# 05-WPT.net
KiCad netlist of a schematic drawn in Altium Designer
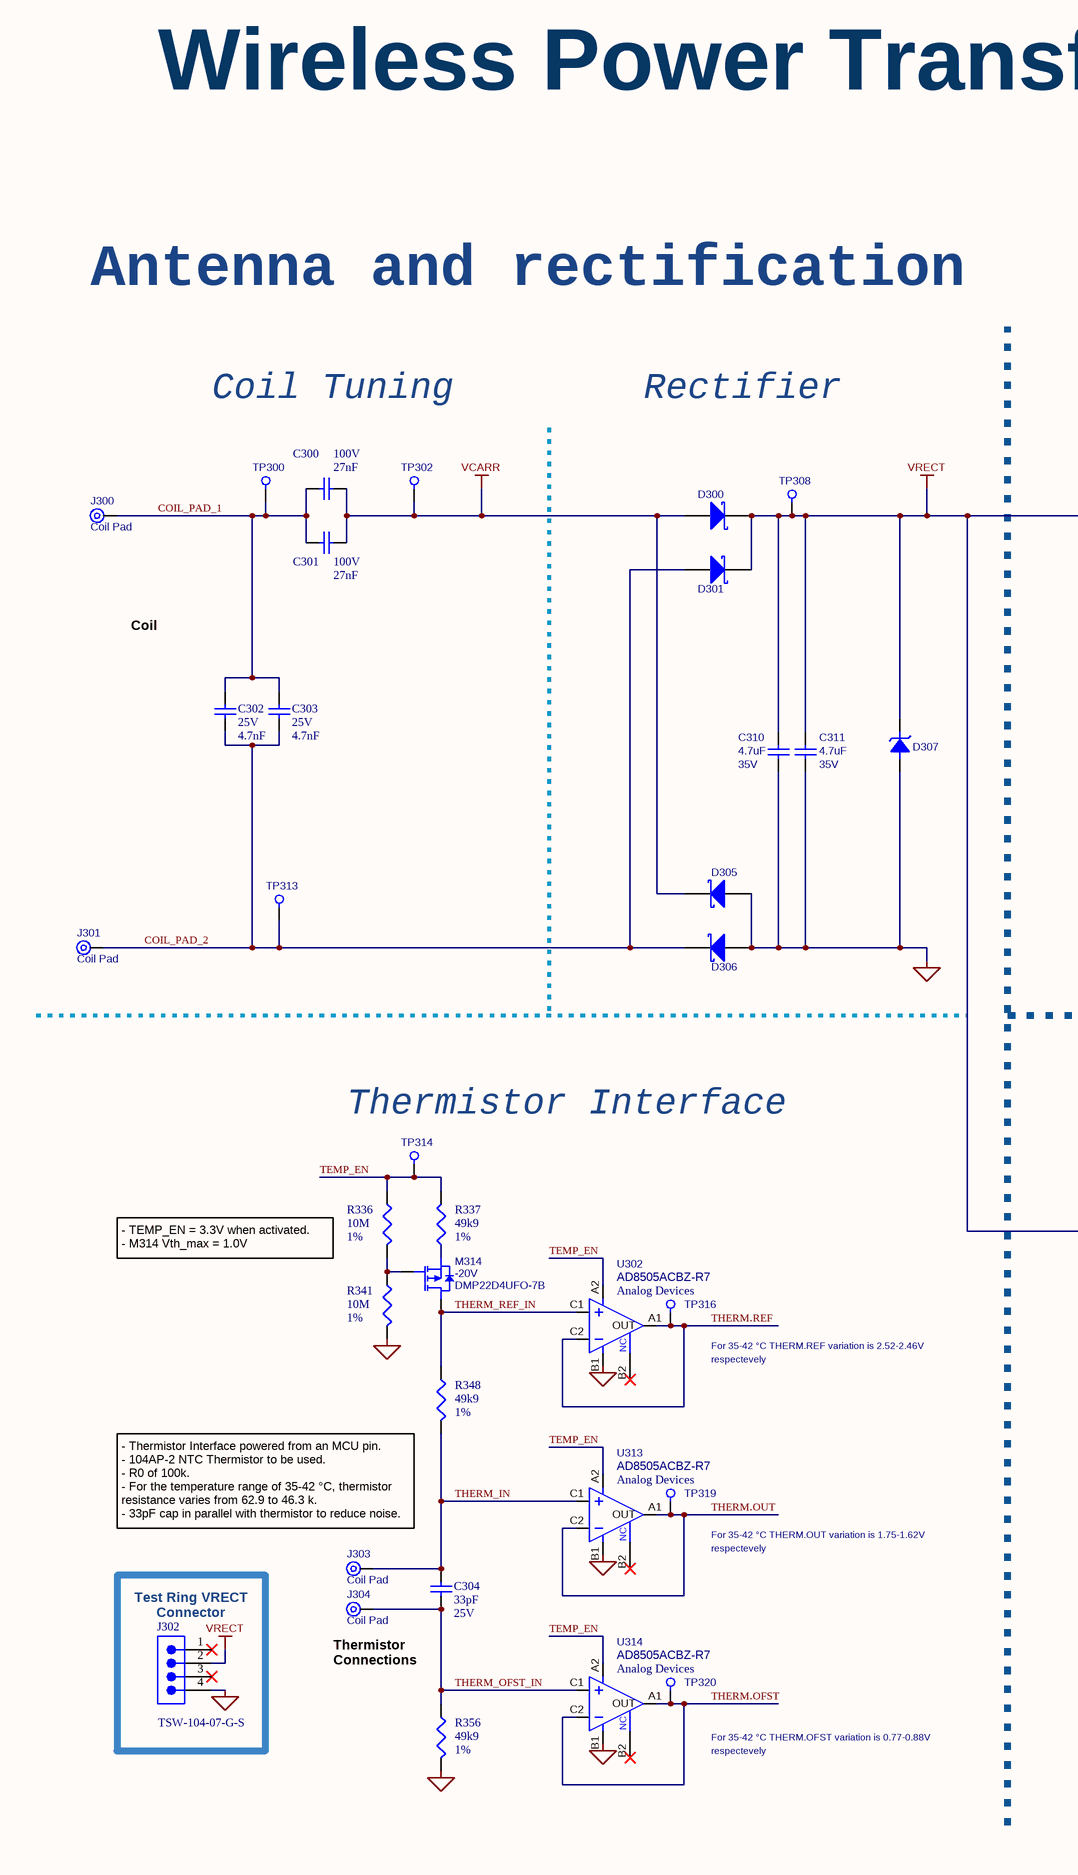
[diagram p0: 05-WPT.SchDoc, left]
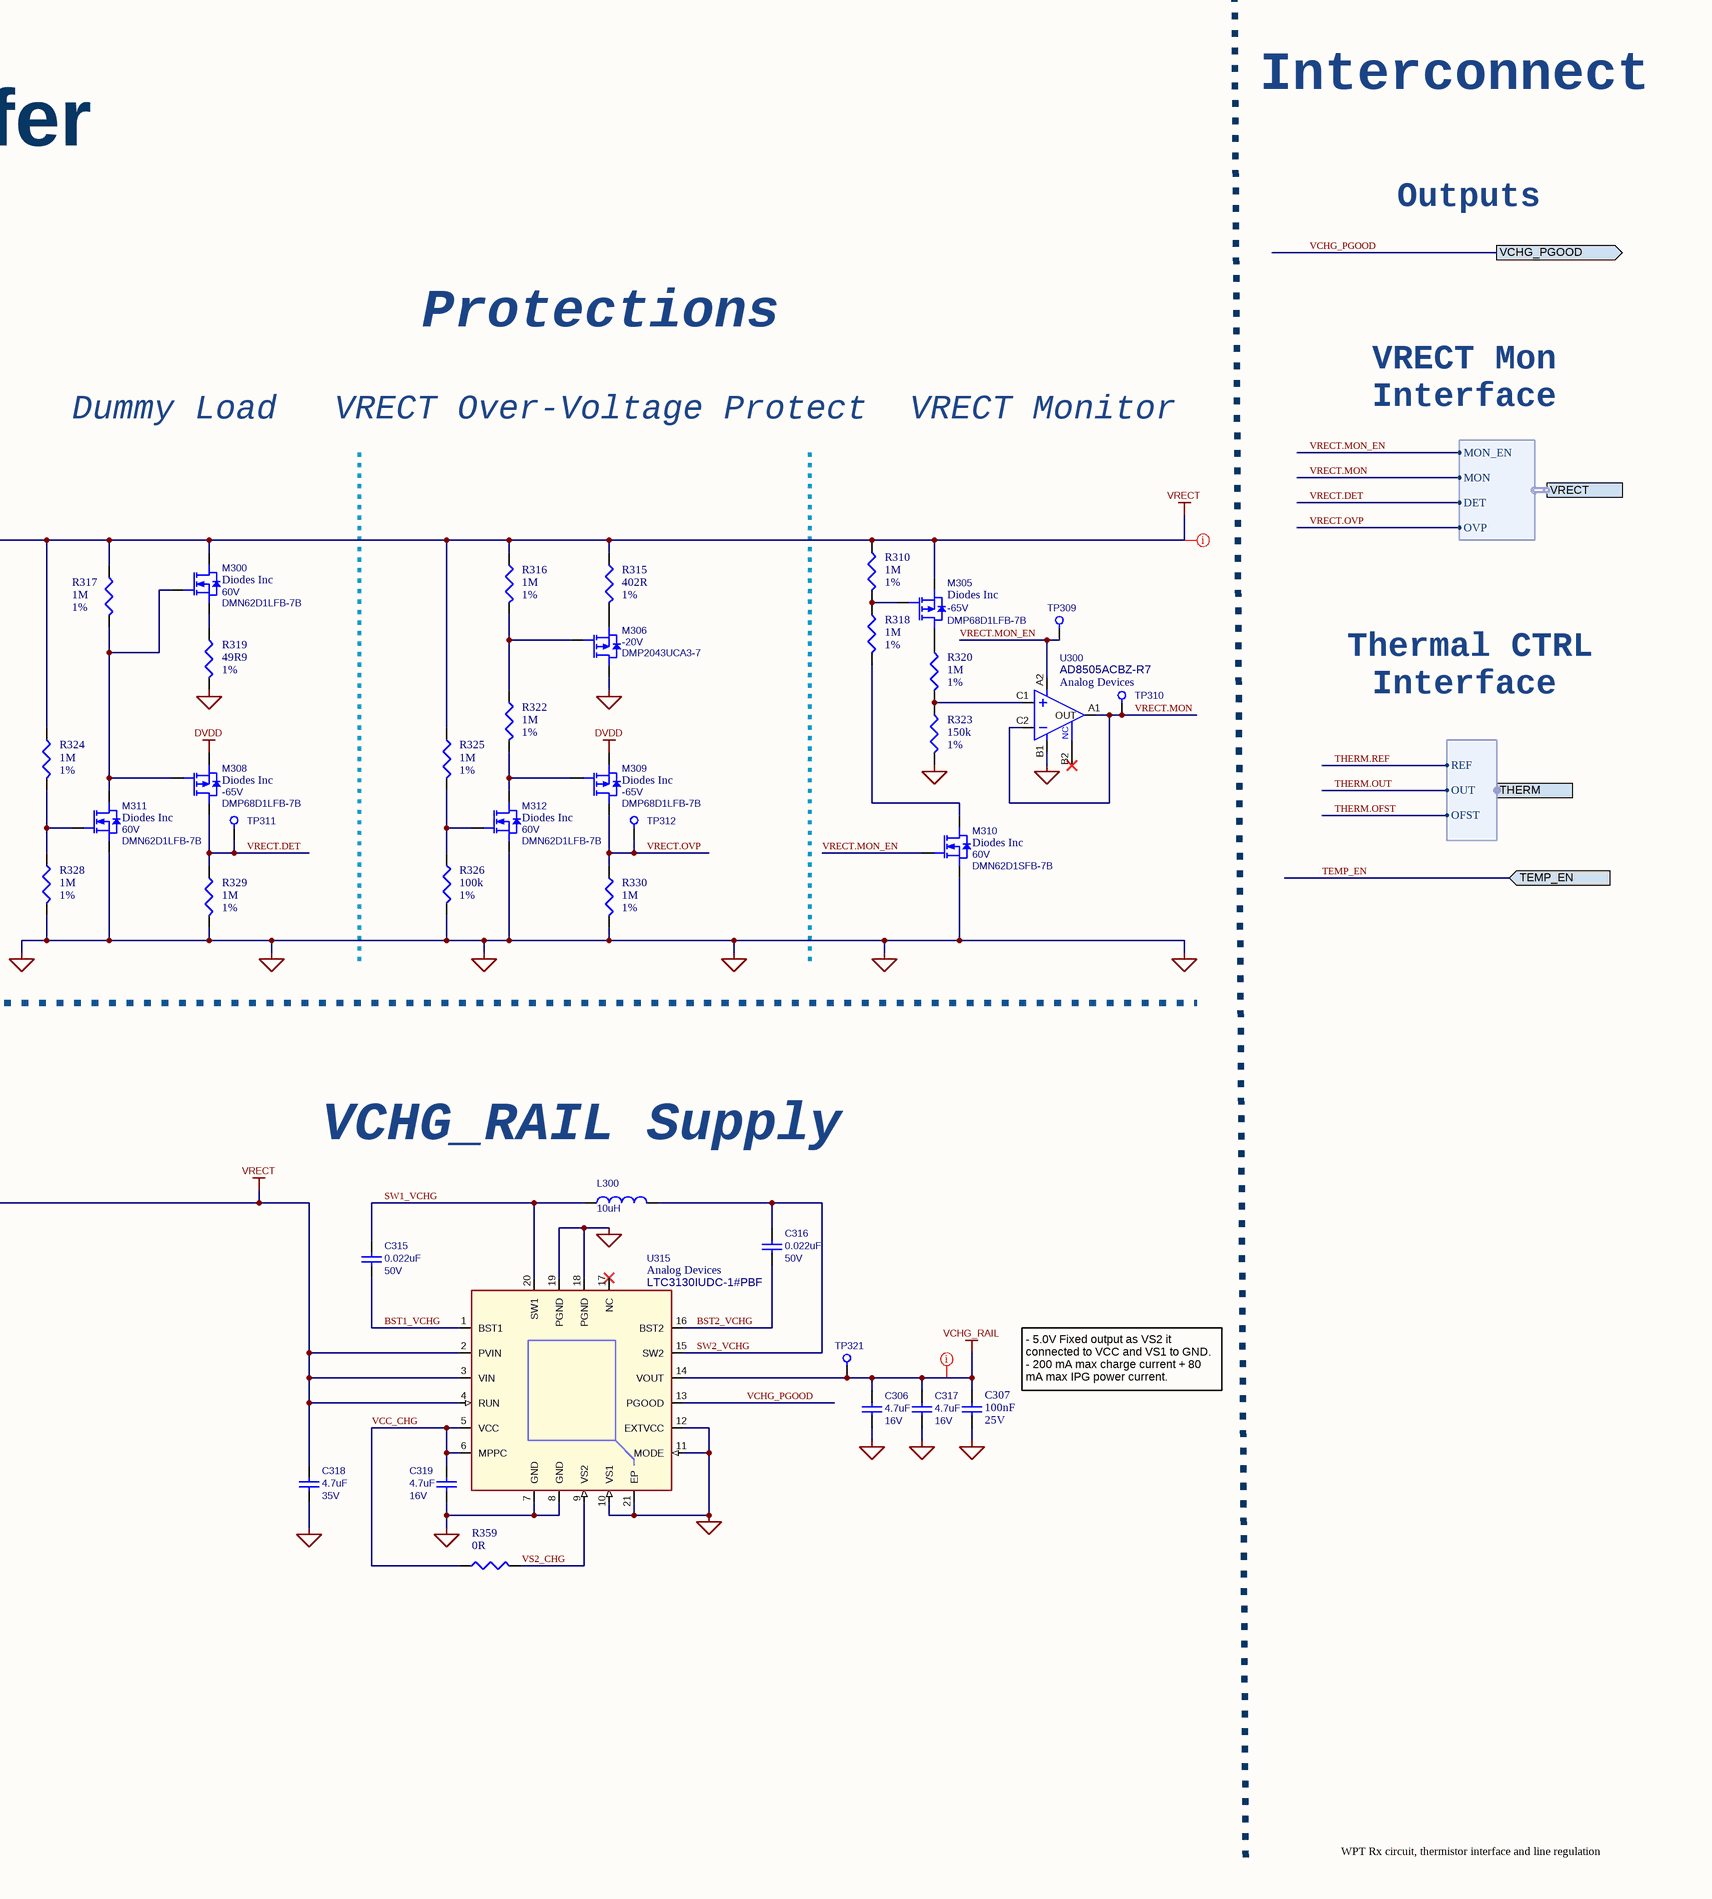
[diagram p1: 05-WPT.SchDoc, right]

(export (version "E")
  (design (tool "Eeschema 10.0.6"))
  (components
    (comp (ref "C300")
      (value "27nF")
      (footprint "CAP0805_REDUCED")
      (description "Capacitor, 27nF, C0G, 100VDC, 2%, 0805, Implant-grade")
      (fields
        (field (name "MANUFACTURER") "Murata")
        (field (name "MANUFACTURER PART NUMBER") "GRM2195C2A273GE01D")
        (field (name "VOLTAGE RATING") "100V")
      )
      (libsource (lib "MP-LIBRARY") (part "GRM2195C2A273GE01D"))
    )
    (comp (ref "C301")
      (value "27nF")
      (footprint "CAP0805_REDUCED")
      (description "Capacitor, 27nF, C0G, 100VDC, 2%, 0805, Implant-grade")
      (fields
        (field (name "MANUFACTURER") "Murata")
        (field (name "MANUFACTURER PART NUMBER") "GRM2195C2A273GE01D")
        (field (name "VOLTAGE RATING") "100V")
      )
      (libsource (lib "MP-LIBRARY") (part "GRM2195C2A273GE01D"))
    )
    (comp (ref "C302")
      (value "4.7nF")
      (footprint "CAP0603_REDUCED")
      (description "Capacitor, 4.7nF, C0G, 25V, 1%, 0603, Implant-grade")
      (fields
        (field (name "MANUFACTURER") "KEMET")
        (field (name "MANUFACTURER PART NUMBER") "C0603C472F3GECTU")
        (field (name "VOLTAGE RATING") "25V")
      )
      (libsource (lib "MP-LIBRARY") (part "C0603C472F3GECTU"))
    )
    (comp (ref "C303")
      (value "4.7nF")
      (footprint "CAP0603_REDUCED")
      (description "Capacitor, 4.7nF, C0G, 25V, 1%, 0603, Implant-grade")
      (fields
        (field (name "MANUFACTURER") "KEMET")
        (field (name "MANUFACTURER PART NUMBER") "C0603C472F3GECTU")
        (field (name "VOLTAGE RATING") "25V")
      )
      (libsource (lib "MP-LIBRARY") (part "C0603C472F3GECTU"))
    )
    (comp (ref "C304")
      (value "33pF")
      (footprint "C0201_C")
      (fields
        (field (name "MANUFACTURER") "Murata")
        (field (name "MANUFACTURER PART NUMBER") "GRM0335C1E330JA01D")
        (field (name "RATED DC VOLTAGE (URDC)") "25V")
      )
      (libsource (lib "MP-LIBRARY") (part "GRM0335C1E330JA01D"))
    )
    (comp (ref "C306")
      (value "4.7uF")
      (footprint "CAP0603_REDUCED")
      (description "Capacitor, 4.7uF, X5R, 16V, 10%, 0603, Implant-grade")
      (fields
        (field (name "MANUFACTURER") "Murata")
        (field (name "RATING") "16V")
        (field (name "MANUFACTURER PART NUMBER") "GRM188R61C475KE11")
      )
      (libsource (lib "MP-LIBRARY") (part "GRM188R61C475KE11"))
    )
    (comp (ref "C307")
      (value "100nF")
      (footprint "C0201_C")
      (fields
        (field (name "MANUFACTURER") "Murata")
        (field (name "MANUFACTURER PART NUMBER") "GRM033R61E104KE14J")
        (field (name "RATED DC VOLTAGE (URDC)") "25V")
      )
      (libsource (lib "MP-LIBRARY") (part "GRM033R61E104KE14J"))
    )
    (comp (ref "C310")
      (value "4.7uF")
      (footprint "CAP0805_REDUCED")
      (description "Capacitor, 4.7uF, X7S, 35V, 10%, 0805, Implant-grade")
      (fields
        (field (name "MANUFACTURER") "Murata")
        (field (name "RATING") "35V")
        (field (name "MANUFACTURER PART NUMBER") "GCM21BC7YA475KE36L")
      )
      (libsource (lib "MP-LIBRARY") (part "GCM21BC7YA475KE36L"))
    )
    (comp (ref "C311")
      (value "4.7uF")
      (footprint "CAP0805_REDUCED")
      (description "Capacitor, 4.7uF, X7S, 35V, 10%, 0805, Implant-grade")
      (fields
        (field (name "MANUFACTURER") "Murata")
        (field (name "RATING") "35V")
        (field (name "MANUFACTURER PART NUMBER") "GCM21BC7YA475KE36L")
      )
      (libsource (lib "MP-LIBRARY") (part "GCM21BC7YA475KE36L"))
    )
    (comp (ref "C315")
      (value "0.022uF")
      (footprint "CAP0402_REDUCED")
      (description "Capacitor, 0.022uF, X7R, 50V, 10%, 0402, Implant-grade")
      (fields
        (field (name "MANUFACTURER") "Murata")
        (field (name "RATING") "50V")
        (field (name "MANUFACTURER PART NUMBER") "GCM155R71H223KA55")
      )
      (libsource (lib "MP-LIBRARY") (part "GCM155R71H223KA55D"))
    )
    (comp (ref "C316")
      (value "0.022uF")
      (footprint "CAP0402_REDUCED")
      (description "Capacitor, 0.022uF, X7R, 50V, 10%, 0402, Implant-grade")
      (fields
        (field (name "MANUFACTURER") "Murata")
        (field (name "RATING") "50V")
        (field (name "MANUFACTURER PART NUMBER") "GCM155R71H223KA55")
      )
      (libsource (lib "MP-LIBRARY") (part "GCM155R71H223KA55D"))
    )
    (comp (ref "C317")
      (value "4.7uF")
      (footprint "CAP0603_REDUCED")
      (description "Capacitor, 4.7uF, X5R, 16V, 10%, 0603, Implant-grade")
      (fields
        (field (name "MANUFACTURER") "Murata")
        (field (name "RATING") "16V")
        (field (name "MANUFACTURER PART NUMBER") "GRM188R61C475KE11")
      )
      (libsource (lib "MP-LIBRARY") (part "GRM188R61C475KE11"))
    )
    (comp (ref "C318")
      (value "4.7uF")
      (footprint "CAP0805_REDUCED")
      (description "Capacitor, 4.7uF, X7S, 35V, 10%, 0805, Implant-grade")
      (fields
        (field (name "MANUFACTURER") "Murata")
        (field (name "RATING") "35V")
        (field (name "MANUFACTURER PART NUMBER") "GCM21BC7YA475KE36L")
      )
      (libsource (lib "MP-LIBRARY") (part "GCM21BC7YA475KE36L"))
    )
    (comp (ref "C319")
      (value "4.7uF")
      (footprint "CAP0603_REDUCED")
      (description "Capacitor, 4.7uF, X5R, 16V, 10%, 0603, Implant-grade")
      (fields
        (field (name "MANUFACTURER") "Murata")
        (field (name "RATING") "16V")
        (field (name "MANUFACTURER PART NUMBER") "GRM188R61C475KE11")
      )
      (libsource (lib "MP-LIBRARY") (part "GRM188R61C475KE11"))
    )
    (comp (ref "D300")
      (value "NSR05T40XV2T5G")
      (footprint "STM_SOD-523_R")
      (description "Schottky, 40V, 500mA, 530mV, SOD-523")
      (fields (field (name "MANUFACTURER") "ON Semiconductor"))
      (libsource (lib "MP-LIBRARY") (part "NSR05T40XV2T5G"))
    )
    (comp (ref "D301")
      (value "NSR05T40XV2T5G")
      (footprint "STM_SOD-523_R")
      (description "Schottky, 40V, 500mA, 530mV, SOD-523")
      (fields (field (name "MANUFACTURER") "ON Semiconductor"))
      (libsource (lib "MP-LIBRARY") (part "NSR05T40XV2T5G"))
    )
    (comp (ref "D305")
      (value "NSR05T40XV2T5G")
      (footprint "STM_SOD-523_R")
      (description "Schottky, 40V, 500mA, 530mV, SOD-523")
      (fields (field (name "MANUFACTURER") "ON Semiconductor"))
      (libsource (lib "MP-LIBRARY") (part "NSR05T40XV2T5G"))
    )
    (comp (ref "D306")
      (value "NSR05T40XV2T5G")
      (footprint "STM_SOD-523_R")
      (description "Schottky, 40V, 500mA, 530mV, SOD-523")
      (fields (field (name "MANUFACTURER") "ON Semiconductor"))
      (libsource (lib "MP-LIBRARY") (part "NSR05T40XV2T5G"))
    )
    (comp (ref "D307")
      (value "BZX884B10L-G3-08")
      (footprint "DFN1006-2A")
      (description "Zener Diode 10 V 300 mW ±2% Surface Mount DFN1006-2A 0402")
      (fields (field (name "MANUFACTURER") "Vishay"))
      (libsource (lib "MP-LIBRARY") (part "BZX884B10L-G3-08"))
    )
    (comp (ref "J300")
      (value "Coil Pad")
      (footprint "FEEDHOLE_20mil")
      (description "Coil TH pad, hole size and ring TBD")
      (libsource (lib "MP-LIBRARY") (part "Coil Pad"))
    )
    (comp (ref "J301")
      (value "Coil Pad")
      (footprint "FEEDHOLE_20mil")
      (description "Coil TH pad, hole size and ring TBD")
      (libsource (lib "MP-LIBRARY") (part "Coil Pad"))
    )
    (comp (ref "J302")
      (value "TSW-104-07-G-S")
      (footprint "SMTC-TSW-104-07-X-S")
      (fields (field (name "MANUFACTURER") "Samtec") (field (name "PARTNUMBER") "TSW-106-07-G-S"))
      (libsource (lib "MP-LIBRARY") (part "TSW-104-07-G-S"))
    )
    (comp (ref "J303")
      (value "Coil Pad")
      (footprint "FEEDHOLE_20mil")
      (description "Coil TH pad, hole size and ring TBD")
      (libsource (lib "MP-LIBRARY") (part "Coil Pad"))
    )
    (comp (ref "J304")
      (value "Coil Pad")
      (footprint "FEEDHOLE_20mil")
      (description "Coil TH pad, hole size and ring TBD")
      (libsource (lib "MP-LIBRARY") (part "Coil Pad"))
    )
    (comp (ref "L300")
      (value "10uH")
      (footprint "WURTH_74438323100_REDUCED")
      (description "Inductor, 10uH, 600mA, 20%, 1008")
      (fields (field (name "MANUFACTURER") "Wurth") (field (name "MANUFACTURER PART NUMBER") "74438323100"))
      (libsource (lib "MP-LIBRARY") (part "74438323100"))
    )
    (comp (ref "M300")
      (value "DMN62D1LFB-7B")
      (footprint "DIODESINC_X1-DFN1006-3")
      (description "MOSFET, N-Chan, 60V, 320mA, DFN1006")
      (fields (field (name "MANUFACTURER") "Diodes Inc") (field (name "RATING") "60V"))
      (libsource (lib "MP-LIBRARY") (part "DMN62D1LFB-7B"))
    )
    (comp (ref "M305")
      (value "DMP68D1LFB-7B")
      (footprint "DIODESINC_X1-DFN1006-3")
      (description "MOSFET, P-chan, -65V, -290mA, DFN1006")
      (fields
        (field (name "MANUFACTURER") "Diodes Inc")
        (field (name "RATING") "-65V")
        (field (name "MANUFACTURER PART NUMBER") "DMP68D1LFB")
      )
      (libsource (lib "MP-LIBRARY") (part "DMP68D1LFB-7B"))
    )
    (comp (ref "M306")
      (value "DMP2043UCA3-7")
      (footprint "DIODESINC_X2-DSN1010-3_CUSTOMPIN")
      (description "MOSFET, P-chan, -20V, -3.4A, DFN1010-3")
      (fields (field (name "MANUFACTURER") "Diodes Inc") (field (name "RATING") "-20V"))
      (libsource (lib "MP-LIBRARY") (part "DMP2043UCA3-7"))
    )
    (comp (ref "M308")
      (value "DMP68D1LFB-7B")
      (footprint "DIODESINC_X1-DFN1006-3")
      (description "MOSFET, P-chan, -65V, -290mA, DFN1006")
      (fields
        (field (name "MANUFACTURER") "Diodes Inc")
        (field (name "RATING") "-65V")
        (field (name "MANUFACTURER PART NUMBER") "DMP68D1LFB")
      )
      (libsource (lib "MP-LIBRARY") (part "DMP68D1LFB-7B"))
    )
    (comp (ref "M309")
      (value "DMP68D1LFB-7B")
      (footprint "DIODESINC_X1-DFN1006-3")
      (description "MOSFET, P-chan, -65V, -290mA, DFN1006")
      (fields
        (field (name "MANUFACTURER") "Diodes Inc")
        (field (name "RATING") "-65V")
        (field (name "MANUFACTURER PART NUMBER") "DMP68D1LFB")
      )
      (libsource (lib "MP-LIBRARY") (part "DMP68D1LFB-7B"))
    )
    (comp (ref "M310")
      (value "DMN62D1SFB-7B")
      (footprint "DIODESINC_X1-DFN1006-3")
      (description "MOSFET, N-Chan, 60V, 300mA, DFN1006")
      (fields (field (name "MANUFACTURER") "Diodes Inc") (field (name "RATING") "60V"))
      (libsource (lib "MP-LIBRARY") (part "DMN62D1SFB-7B"))
    )
    (comp (ref "M311")
      (value "DMN62D1LFB-7B")
      (footprint "DIODESINC_X1-DFN1006-3")
      (description "MOSFET, N-Chan, 60V, 320mA, DFN1006")
      (fields (field (name "MANUFACTURER") "Diodes Inc") (field (name "RATING") "60V"))
      (libsource (lib "MP-LIBRARY") (part "DMN62D1LFB-7B"))
    )
    (comp (ref "M312")
      (value "DMN62D1LFB-7B")
      (footprint "DIODESINC_X1-DFN1006-3")
      (description "MOSFET, N-Chan, 60V, 320mA, DFN1006")
      (fields (field (name "MANUFACTURER") "Diodes Inc") (field (name "RATING") "60V"))
      (libsource (lib "MP-LIBRARY") (part "DMN62D1LFB-7B"))
    )
    (comp (ref "M314")
      (value "DMP22D4UFO-7B")
      (footprint "DIODESINC_X2-DFN0604-3")
      (description "MOSFET, P-chan, -20V, -383mA, DFN0604")
      (fields (field (name "MANUFACTURER") "Diodes Inc") (field (name "RATING") "-20V"))
      (libsource (lib "MP-LIBRARY") (part "DMP22D4UFO-7B"))
    )
    (comp (ref "R310")
      (value "1M")
      (footprint "R0201_C")
      (fields
        (field (name "MANUFACTURER") "Vishay")
        (field (name "MANUFACTURER PART NUMBER") "CRCW02011M00FNED")
        (field (name "TOLERANCE") "1%")
        (field (name "POWER") "50mW")
      )
      (libsource (lib "MP-LIBRARY") (part "CRCW02011M00FNED"))
    )
    (comp (ref "R315")
      (value "402R")
      (footprint "R0201_C")
      (fields
        (field (name "MANUFACTURER") "Vishay")
        (field (name "MANUFACTURER PART NUMBER") "CRCW0201402RFNED")
        (field (name "TOLERANCE") "1%")
        (field (name "POWER") "50mW")
      )
      (libsource (lib "MP-LIBRARY") (part "CRCW0201402RFNED"))
    )
    (comp (ref "R316")
      (value "1M")
      (footprint "R0201_C")
      (fields
        (field (name "MANUFACTURER") "Vishay")
        (field (name "MANUFACTURER PART NUMBER") "CRCW02011M00FNED")
        (field (name "TOLERANCE") "1%")
        (field (name "POWER") "50mW")
      )
      (libsource (lib "MP-LIBRARY") (part "CRCW02011M00FNED"))
    )
    (comp (ref "R317")
      (value "1M")
      (footprint "R0201_C")
      (fields
        (field (name "MANUFACTURER") "Vishay")
        (field (name "MANUFACTURER PART NUMBER") "CRCW02011M00FNED")
        (field (name "TOLERANCE") "1%")
        (field (name "POWER") "50mW")
      )
      (libsource (lib "MP-LIBRARY") (part "CRCW02011M00FNED"))
    )
    (comp (ref "R318")
      (value "1M")
      (footprint "R0201_C")
      (fields
        (field (name "MANUFACTURER") "Vishay")
        (field (name "MANUFACTURER PART NUMBER") "CRCW02011M00FNED")
        (field (name "TOLERANCE") "1%")
        (field (name "POWER") "50mW")
      )
      (libsource (lib "MP-LIBRARY") (part "CRCW02011M00FNED"))
    )
    (comp (ref "R319")
      (value "49R9")
      (footprint "R0201_C")
      (fields
        (field (name "MANUFACTURER") "Vishay")
        (field (name "MANUFACTURER PART NUMBER") "CRCW020149R9FNED")
        (field (name "TOLERANCE") "1%")
        (field (name "POWER") "50mW")
      )
      (libsource (lib "MP-LIBRARY") (part "CRCW020149R9FNED"))
    )
    (comp (ref "R320")
      (value "1M")
      (footprint "R0201_C")
      (fields
        (field (name "MANUFACTURER") "Vishay")
        (field (name "MANUFACTURER PART NUMBER") "CRCW02011M00FNED")
        (field (name "TOLERANCE") "1%")
        (field (name "POWER") "50mW")
      )
      (libsource (lib "MP-LIBRARY") (part "CRCW02011M00FNED"))
    )
    (comp (ref "R322")
      (value "1M")
      (footprint "R0201_C")
      (fields
        (field (name "MANUFACTURER") "Vishay")
        (field (name "MANUFACTURER PART NUMBER") "CRCW02011M00FNED")
        (field (name "TOLERANCE") "1%")
        (field (name "POWER") "50mW")
      )
      (libsource (lib "MP-LIBRARY") (part "CRCW02011M00FNED"))
    )
    (comp (ref "R323")
      (value "150k")
      (footprint "R0201_C")
      (fields
        (field (name "MANUFACTURER") "Vishay")
        (field (name "MANUFACTURER PART NUMBER") "CRCW0201150KFNED")
        (field (name "TOLERANCE") "1%")
        (field (name "POWER") "50mW")
      )
      (libsource (lib "MP-LIBRARY") (part "CRCW0201150KFNED"))
    )
    (comp (ref "R324")
      (value "1M")
      (footprint "R0201_C")
      (fields
        (field (name "MANUFACTURER") "Vishay")
        (field (name "MANUFACTURER PART NUMBER") "CRCW02011M00FNED")
        (field (name "TOLERANCE") "1%")
        (field (name "POWER") "50mW")
      )
      (libsource (lib "MP-LIBRARY") (part "CRCW02011M00FNED"))
    )
    (comp (ref "R325")
      (value "1M")
      (footprint "R0201_C")
      (fields
        (field (name "MANUFACTURER") "Vishay")
        (field (name "MANUFACTURER PART NUMBER") "CRCW02011M00FNED")
        (field (name "TOLERANCE") "1%")
        (field (name "POWER") "50mW")
      )
      (libsource (lib "MP-LIBRARY") (part "CRCW02011M00FNED"))
    )
    (comp (ref "R326")
      (value "100k")
      (footprint "R0201_C")
      (fields
        (field (name "MANUFACTURER") "Vishay")
        (field (name "MANUFACTURER PART NUMBER") "CRCW0201100KFNED")
        (field (name "TOLERANCE") "1%")
        (field (name "POWER") "50mW")
      )
      (libsource (lib "MP-LIBRARY") (part "CRCW0201100KFNED"))
    )
    (comp (ref "R328")
      (value "1M")
      (footprint "R0201_C")
      (fields
        (field (name "MANUFACTURER") "Vishay")
        (field (name "MANUFACTURER PART NUMBER") "CRCW02011M00FNED")
        (field (name "TOLERANCE") "1%")
        (field (name "POWER") "50mW")
      )
      (libsource (lib "MP-LIBRARY") (part "CRCW02011M00FNED"))
    )
    (comp (ref "R329")
      (value "1M")
      (footprint "R0201_C")
      (fields
        (field (name "MANUFACTURER") "Vishay")
        (field (name "MANUFACTURER PART NUMBER") "CRCW02011M00FNED")
        (field (name "TOLERANCE") "1%")
        (field (name "POWER") "50mW")
      )
      (libsource (lib "MP-LIBRARY") (part "CRCW02011M00FNED"))
    )
    (comp (ref "R330")
      (value "1M")
      (footprint "R0201_C")
      (fields
        (field (name "MANUFACTURER") "Vishay")
        (field (name "MANUFACTURER PART NUMBER") "CRCW02011M00FNED")
        (field (name "TOLERANCE") "1%")
        (field (name "POWER") "50mW")
      )
      (libsource (lib "MP-LIBRARY") (part "CRCW02011M00FNED"))
    )
    (comp (ref "R336")
      (value "10M")
      (footprint "R0201_C")
      (fields
        (field (name "MANUFACTURER") "Vishay Draloric")
        (field (name "MANUFACTURER PART NUMBER") "CRCW020110M0FNED")
        (field (name "TOLERANCE") "1%")
        (field (name "POWER") "50mW")
      )
      (libsource (lib "MP-LIBRARY") (part "CRCW020110M0FNED"))
    )
    (comp (ref "R337")
      (value "49k9")
      (footprint "R0201_C")
      (fields
        (field (name "MANUFACTURER") "Vishay")
        (field (name "MANUFACTURER PART NUMBER") "CRCW020149K9FNED")
        (field (name "TOLERANCE") "1%")
        (field (name "POWER") "50mW")
      )
      (libsource (lib "MP-LIBRARY") (part "CRCW020149K9FNED"))
    )
    (comp (ref "R341")
      (value "10M")
      (footprint "R0201_C")
      (fields
        (field (name "MANUFACTURER") "Vishay Draloric")
        (field (name "MANUFACTURER PART NUMBER") "CRCW020110M0FNED")
        (field (name "TOLERANCE") "1%")
        (field (name "POWER") "50mW")
      )
      (libsource (lib "MP-LIBRARY") (part "CRCW020110M0FNED"))
    )
    (comp (ref "R348")
      (value "49k9")
      (footprint "R0201_C")
      (fields
        (field (name "MANUFACTURER") "Vishay")
        (field (name "MANUFACTURER PART NUMBER") "CRCW020149K9FNED")
        (field (name "TOLERANCE") "1%")
        (field (name "POWER") "50mW")
      )
      (libsource (lib "MP-LIBRARY") (part "CRCW020149K9FNED"))
    )
    (comp (ref "R356")
      (value "49k9")
      (footprint "R0201_C")
      (fields
        (field (name "MANUFACTURER") "Vishay")
        (field (name "MANUFACTURER PART NUMBER") "CRCW020149K9FNED")
        (field (name "TOLERANCE") "1%")
        (field (name "POWER") "50mW")
      )
      (libsource (lib "MP-LIBRARY") (part "CRCW020149K9FNED"))
    )
    (comp (ref "R359")
      (value "0R")
      (footprint "R0201_C")
      (description "Fixed Resistor, Metal Glaze/thick Film, 0.05W, 0ohm, Surface Mount, 0201")
      (fields
        (field (name "MANUFACTURER") "Vishay")
        (field (name "MANUFACTURER PART NUMBER") "CRCW02010000Z0ED")
      )
      (libsource (lib "MP-LIBRARY") (part "CRCW02010000Z0ED"))
    )
    (comp (ref "TP300")
      (value "Test Point")
      (footprint "testpad_0.9mm")
      (description "Test pad, 0.90mm circular pad")
      (libsource (lib "MP-LIBRARY") (part "Test Point"))
    )
    (comp (ref "TP302")
      (value "Test Point")
      (footprint "testpad_0.9mm")
      (description "Test pad, 0.90mm circular pad")
      (libsource (lib "MP-LIBRARY") (part "Test Point"))
    )
    (comp (ref "TP308")
      (value "Test Point")
      (footprint "testpad_0.9mm")
      (description "Test pad, 0.90mm circular pad")
      (libsource (lib "MP-LIBRARY") (part "Test Point"))
    )
    (comp (ref "TP309")
      (value "Test Point")
      (footprint "testpad_0.9mm")
      (description "Test pad, 0.90mm circular pad")
      (libsource (lib "MP-LIBRARY") (part "Test Point"))
    )
    (comp (ref "TP310")
      (value "Test Point")
      (footprint "testpad_0.9mm")
      (description "Test pad, 0.90mm circular pad")
      (libsource (lib "MP-LIBRARY") (part "Test Point"))
    )
    (comp (ref "TP311")
      (value "Test Point")
      (footprint "testpad_0.9mm")
      (description "Test pad, 0.90mm circular pad")
      (libsource (lib "MP-LIBRARY") (part "Test Point"))
    )
    (comp (ref "TP312")
      (value "Test Point")
      (footprint "testpad_0.9mm")
      (description "Test pad, 0.90mm circular pad")
      (libsource (lib "MP-LIBRARY") (part "Test Point"))
    )
    (comp (ref "TP313")
      (value "Test Point")
      (footprint "testpad_0.9mm")
      (description "Test pad, 0.90mm circular pad")
      (libsource (lib "MP-LIBRARY") (part "Test Point"))
    )
    (comp (ref "TP314")
      (value "Test Point")
      (footprint "testpad_0.9mm")
      (description "Test pad, 0.90mm circular pad")
      (libsource (lib "MP-LIBRARY") (part "Test Point"))
    )
    (comp (ref "TP316")
      (value "Test Point")
      (footprint "testpad_0.9mm")
      (description "Test pad, 0.90mm circular pad")
      (libsource (lib "MP-LIBRARY") (part "Test Point"))
    )
    (comp (ref "TP319")
      (value "Test Point")
      (footprint "testpad_0.9mm")
      (description "Test pad, 0.90mm circular pad")
      (libsource (lib "MP-LIBRARY") (part "Test Point"))
    )
    (comp (ref "TP320")
      (value "Test Point")
      (footprint "testpad_0.9mm")
      (description "Test pad, 0.90mm circular pad")
      (libsource (lib "MP-LIBRARY") (part "Test Point"))
    )
    (comp (ref "TP321")
      (value "Test Point")
      (footprint "testpad_0.9mm")
      (description "Test pad, 0.90mm circular pad")
      (libsource (lib "MP-LIBRARY") (part "Test Point"))
    )
    (comp (ref "U300")
      (value "AD8505ACBZ-R7")
      (footprint "AD8505ACBZ-R7")
      (description "Op Amp, Rail-to-Rail, 95kHz, WLCSP-6")
      (fields (field (name "MANUFACTURER") "Analog Devices"))
      (libsource (lib "MP-LIBRARY") (part "AD8505ACBZ-R7"))
    )
    (comp (ref "U302")
      (value "AD8505ACBZ-R7")
      (footprint "AD8505ACBZ-R7")
      (description "Op Amp, Rail-to-Rail, 95kHz, WLCSP-6")
      (fields (field (name "MANUFACTURER") "Analog Devices"))
      (libsource (lib "MP-LIBRARY") (part "AD8505ACBZ-R7"))
    )
    (comp (ref "U313")
      (value "AD8505ACBZ-R7")
      (footprint "AD8505ACBZ-R7")
      (description "Op Amp, Rail-to-Rail, 95kHz, WLCSP-6")
      (fields (field (name "MANUFACTURER") "Analog Devices"))
      (libsource (lib "MP-LIBRARY") (part "AD8505ACBZ-R7"))
    )
    (comp (ref "U314")
      (value "AD8505ACBZ-R7")
      (footprint "AD8505ACBZ-R7")
      (description "Op Amp, Rail-to-Rail, 95kHz, WLCSP-6")
      (fields (field (name "MANUFACTURER") "Analog Devices"))
      (libsource (lib "MP-LIBRARY") (part "AD8505ACBZ-R7"))
    )
    (comp (ref "U315")
      (value "LTC3130IUDC-1#PBF")
      (footprint "LT_UDC-20_REDUCED")
      (description "Buck-Boost Converter, Selectable Voltage, QFN-20")
      (fields (field (name "MANUFACTURER") "Analog Devices"))
      (libsource (lib "MP-LIBRARY") (part "LTC3130IUDC-1#PBF"))
    )
  )
  (nets
    (net (code "4") (name "/BST1_VCHG") (class "Default")
      (node (ref "C315") (pin "1") (pinfunction "1_1") (pintype "passive"))
      (node (ref "U315") (pin "1") (pinfunction "BST1_1") (pintype "passive"))
    )
    (net (code "5") (name "/BST2_VCHG") (class "Default")
      (node (ref "C316") (pin "1") (pinfunction "1_1") (pintype "passive"))
      (node (ref "U315") (pin "16") (pinfunction "BST2_16") (pintype "passive"))
    )
    (net (code "6") (name "/COIL_PAD_1") (class "Default")
      (node (ref "C300") (pin "1") (pinfunction "1_1") (pintype "passive"))
      (node (ref "C301") (pin "1") (pinfunction "1_1") (pintype "passive"))
      (node (ref "C302") (pin "2") (pinfunction "2_2") (pintype "passive"))
      (node (ref "C303") (pin "2") (pinfunction "2_2") (pintype "passive"))
      (node (ref "J300") (pin "1") (pinfunction "1_1") (pintype "passive"))
      (node (ref "TP300") (pin "1") (pinfunction "1_1") (pintype "passive"))
    )
    (net (code "7") (name "/COIL_PAD_2") (class "Default")
      (node (ref "C302") (pin "1") (pinfunction "1_1") (pintype "passive"))
      (node (ref "C303") (pin "1") (pinfunction "1_1") (pintype "passive"))
      (node (ref "D301") (pin "2") (pinfunction "A_2") (pintype "passive"))
      (node (ref "D306") (pin "1") (pinfunction "K_1") (pintype "passive"))
      (node (ref "J301") (pin "1") (pinfunction "1_1") (pintype "passive"))
      (node (ref "TP313") (pin "1") (pinfunction "1_1") (pintype "passive"))
    )
    (net (code "8") (name "/MON") (class "Default")
      (node (ref "TP310") (pin "1") (pinfunction "1_1") (pintype "passive"))
      (node (ref "U300") (pin "A1") (pinfunction "OUT_A1") (pintype "passive"))
      (node (ref "U300") (pin "C2") (pinfunction "IN-_C2") (pintype "passive"))
    )
    (net (code "9") (name "/SW1_VCHG") (class "Default")
      (node (ref "C315") (pin "2") (pinfunction "2_2") (pintype "passive"))
      (node (ref "L300") (pin "1") (pinfunction "1_1") (pintype "passive"))
      (node (ref "U315") (pin "20") (pinfunction "SW1_20") (pintype "passive"))
    )
    (net (code "10") (name "/SW2_VCHG") (class "Default")
      (node (ref "C316") (pin "2") (pinfunction "2_2") (pintype "passive"))
      (node (ref "L300") (pin "2") (pinfunction "2_2") (pintype "passive"))
      (node (ref "U315") (pin "15") (pinfunction "SW2_15") (pintype "passive"))
    )
    (net (code "11") (name "/TEMP_EN") (class "Default")
      (node (ref "R336") (pin "1") (pinfunction "1_1") (pintype "passive"))
      (node (ref "R337") (pin "2") (pinfunction "2_2") (pintype "passive"))
      (node (ref "TP314") (pin "1") (pinfunction "1_1") (pintype "passive"))
      (node (ref "U302") (pin "A2") (pinfunction "V+_A2") (pintype "passive"))
      (node (ref "U313") (pin "A2") (pinfunction "V+_A2") (pintype "passive"))
      (node (ref "U314") (pin "A2") (pinfunction "V+_A2") (pintype "passive"))
    )
    (net (code "12") (name "/THERM.OFST") (class "Default")
      (node (ref "TP320") (pin "1") (pinfunction "1_1") (pintype "passive"))
      (node (ref "U314") (pin "A1") (pinfunction "OUT_A1") (pintype "passive"))
      (node (ref "U314") (pin "C2") (pinfunction "IN-_C2") (pintype "passive"))
    )
    (net (code "13") (name "/THERM.OUT") (class "Default")
      (node (ref "TP319") (pin "1") (pinfunction "1_1") (pintype "passive"))
      (node (ref "U313") (pin "A1") (pinfunction "OUT_A1") (pintype "passive"))
      (node (ref "U313") (pin "C2") (pinfunction "IN-_C2") (pintype "passive"))
    )
    (net (code "14") (name "/THERM.REF") (class "Default")
      (node (ref "TP316") (pin "1") (pinfunction "1_1") (pintype "passive"))
      (node (ref "U302") (pin "A1") (pinfunction "OUT_A1") (pintype "passive"))
      (node (ref "U302") (pin "C2") (pinfunction "IN-_C2") (pintype "passive"))
    )
    (net (code "15") (name "/THERM_IN") (class "Default")
      (node (ref "C304") (pin "2") (pinfunction "2_2") (pintype "passive"))
      (node (ref "J303") (pin "1") (pinfunction "1_1") (pintype "passive"))
      (node (ref "R348") (pin "2") (pinfunction "2_2") (pintype "passive"))
      (node (ref "U313") (pin "C1") (pinfunction "IN+_C1") (pintype "passive"))
    )
    (net (code "16") (name "/THERM_OFST_IN") (class "Default")
      (node (ref "C304") (pin "1") (pinfunction "1_1") (pintype "passive"))
      (node (ref "J304") (pin "1") (pinfunction "1_1") (pintype "passive"))
      (node (ref "R356") (pin "1") (pinfunction "1_1") (pintype "passive"))
      (node (ref "U314") (pin "C1") (pinfunction "IN+_C1") (pintype "passive"))
    )
    (net (code "17") (name "/THERM_REF_IN") (class "Default")
      (node (ref "M314") (pin "3") (pinfunction "D_3") (pintype "passive"))
      (node (ref "R348") (pin "1") (pinfunction "1_1") (pintype "passive"))
      (node (ref "U302") (pin "C1") (pinfunction "IN+_C1") (pintype "passive"))
    )
    (net (code "18") (name "/VCC_CHG") (class "Default")
      (node (ref "C319") (pin "1") (pinfunction "1_1") (pintype "passive"))
      (node (ref "R359") (pin "1") (pinfunction "1_1") (pintype "passive"))
      (node (ref "U315") (pin "5") (pinfunction "VCC_5") (pintype "power_in"))
      (node (ref "U315") (pin "6") (pinfunction "MPPC_6") (pintype "passive"))
    )
    (net (code "19") (name "/VCHG_PGOOD") (class "Default")
      (node (ref "U315") (pin "13") (pinfunction "PGOOD_13") (pintype "open_collector"))
    )
    (net (code "20") (name "/VRECT.DET") (class "Default")
      (node (ref "M308") (pin "3") (pinfunction "D_3") (pintype "passive"))
      (node (ref "R329") (pin "1") (pinfunction "1_1") (pintype "passive"))
      (node (ref "TP311") (pin "1") (pinfunction "1_1") (pintype "passive"))
    )
    (net (code "21") (name "/VRECT.MON_EN") (class "Default")
      (node (ref "M310") (pin "1") (pinfunction "G_1") (pintype "passive"))
      (node (ref "TP309") (pin "1") (pinfunction "1_1") (pintype "passive"))
      (node (ref "U300") (pin "A2") (pinfunction "V+_A2") (pintype "passive"))
    )
    (net (code "22") (name "/VRECT.OVP") (class "Default")
      (node (ref "M309") (pin "3") (pinfunction "D_3") (pintype "passive"))
      (node (ref "R330") (pin "1") (pinfunction "1_1") (pintype "passive"))
      (node (ref "TP312") (pin "1") (pinfunction "1_1") (pintype "passive"))
    )
    (net (code "23") (name "/VS2_CHG") (class "Default")
      (node (ref "R359") (pin "2") (pinfunction "2_2") (pintype "passive"))
      (node (ref "U315") (pin "9") (pinfunction "VS2_9") (pintype "input"))
    )
    (net (code "26") (name "DVDD") (class "Default")
      (node (ref "M308") (pin "2") (pinfunction "S_2") (pintype "passive"))
      (node (ref "M309") (pin "2") (pinfunction "S_2") (pintype "passive"))
    )
    (net (code "27") (name "GND") (class "Default")
      (node (ref "C306") (pin "2") (pinfunction "2_2") (pintype "passive"))
      (node (ref "C307") (pin "1") (pinfunction "1_1") (pintype "passive"))
      (node (ref "C310") (pin "1") (pinfunction "1_1") (pintype "passive"))
      (node (ref "C311") (pin "1") (pinfunction "1_1") (pintype "passive"))
      (node (ref "C317") (pin "2") (pinfunction "2_2") (pintype "passive"))
      (node (ref "C318") (pin "1") (pinfunction "1_1") (pintype "passive"))
      (node (ref "C319") (pin "2") (pinfunction "2_2") (pintype "passive"))
      (node (ref "D305") (pin "2") (pinfunction "A_2") (pintype "passive"))
      (node (ref "D306") (pin "2") (pinfunction "A_2") (pintype "passive"))
      (node (ref "D307") (pin "1") (pinfunction "1_1") (pintype "passive"))
      (node (ref "J302") (pin "4") (pinfunction "4_4") (pintype "passive"))
      (node (ref "M306") (pin "1") (pinfunction "D_1") (pintype "passive"))
      (node (ref "M310") (pin "2") (pinfunction "S_2") (pintype "passive"))
      (node (ref "M311") (pin "2") (pinfunction "S_2") (pintype "passive"))
      (node (ref "M312") (pin "2") (pinfunction "S_2") (pintype "passive"))
      (node (ref "R319") (pin "2") (pinfunction "2_2") (pintype "passive"))
      (node (ref "R323") (pin "2") (pinfunction "2_2") (pintype "passive"))
      (node (ref "R326") (pin "2") (pinfunction "2_2") (pintype "passive"))
      (node (ref "R328") (pin "2") (pinfunction "2_2") (pintype "passive"))
      (node (ref "R329") (pin "2") (pinfunction "2_2") (pintype "passive"))
      (node (ref "R330") (pin "2") (pinfunction "2_2") (pintype "passive"))
      (node (ref "R341") (pin "2") (pinfunction "2_2") (pintype "passive"))
      (node (ref "R356") (pin "2") (pinfunction "2_2") (pintype "passive"))
      (node (ref "U300") (pin "B1") (pinfunction "V-_B1") (pintype "power_in"))
      (node (ref "U302") (pin "B1") (pinfunction "V-_B1") (pintype "power_in"))
      (node (ref "U313") (pin "B1") (pinfunction "V-_B1") (pintype "power_in"))
      (node (ref "U314") (pin "B1") (pinfunction "V-_B1") (pintype "power_in"))
      (node (ref "U315") (pin "10") (pinfunction "VS1_10") (pintype "input"))
      (node (ref "U315") (pin "11") (pinfunction "MODE_11") (pintype "input"))
      (node (ref "U315") (pin "12") (pinfunction "EXTVCC_12") (pintype "power_in"))
      (node (ref "U315") (pin "18") (pinfunction "PGND_18") (pintype "power_in"))
      (node (ref "U315") (pin "19") (pinfunction "PGND_19") (pintype "power_in"))
      (node (ref "U315") (pin "21") (pinfunction "EP_21") (pintype "power_in"))
      (node (ref "U315") (pin "7") (pinfunction "GND_7") (pintype "power_in"))
      (node (ref "U315") (pin "8") (pinfunction "GND_8") (pintype "power_in"))
    )
    (net (code "28") (name "Net-(M300-G)") (class "Default")
      (node (ref "M300") (pin "1") (pinfunction "G_1") (pintype "passive"))
      (node (ref "M308") (pin "1") (pinfunction "G_1") (pintype "passive"))
      (node (ref "M311") (pin "3") (pinfunction "D_3") (pintype "passive"))
      (node (ref "R317") (pin "2") (pinfunction "2_2") (pintype "passive"))
    )
    (net (code "29") (name "Net-(M300-S)") (class "Default")
      (node (ref "M300") (pin "2") (pinfunction "S_2") (pintype "passive"))
      (node (ref "R319") (pin "1") (pinfunction "1_1") (pintype "passive"))
    )
    (net (code "30") (name "Net-(M305-D)") (class "Default")
      (node (ref "M305") (pin "3") (pinfunction "D_3") (pintype "passive"))
      (node (ref "R320") (pin "1") (pinfunction "1_1") (pintype "passive"))
    )
    (net (code "31") (name "Net-(M305-G)") (class "Default")
      (node (ref "M305") (pin "1") (pinfunction "G_1") (pintype "passive"))
      (node (ref "R310") (pin "2") (pinfunction "2_2") (pintype "passive"))
      (node (ref "R318") (pin "1") (pinfunction "1_1") (pintype "passive"))
    )
    (net (code "32") (name "Net-(M306-G)") (class "Default")
      (node (ref "M306") (pin "2") (pinfunction "G_2") (pintype "passive"))
      (node (ref "R316") (pin "2") (pinfunction "2_2") (pintype "passive"))
      (node (ref "R322") (pin "1") (pinfunction "1_1") (pintype "passive"))
    )
    (net (code "33") (name "Net-(M306-S)") (class "Default")
      (node (ref "M306") (pin "3") (pinfunction "S_3") (pintype "passive"))
      (node (ref "R315") (pin "2") (pinfunction "2_2") (pintype "passive"))
    )
    (net (code "34") (name "Net-(M309-G)") (class "Default")
      (node (ref "M309") (pin "1") (pinfunction "G_1") (pintype "passive"))
      (node (ref "M312") (pin "3") (pinfunction "D_3") (pintype "passive"))
      (node (ref "R322") (pin "2") (pinfunction "2_2") (pintype "passive"))
    )
    (net (code "35") (name "Net-(M310-D)") (class "Default")
      (node (ref "M310") (pin "3") (pinfunction "D_3") (pintype "passive"))
      (node (ref "R318") (pin "2") (pinfunction "2_2") (pintype "passive"))
    )
    (net (code "36") (name "Net-(M311-G)") (class "Default")
      (node (ref "M311") (pin "1") (pinfunction "G_1") (pintype "passive"))
      (node (ref "R324") (pin "2") (pinfunction "2_2") (pintype "passive"))
      (node (ref "R328") (pin "1") (pinfunction "1_1") (pintype "passive"))
    )
    (net (code "37") (name "Net-(M312-G)") (class "Default")
      (node (ref "M312") (pin "1") (pinfunction "G_1") (pintype "passive"))
      (node (ref "R325") (pin "2") (pinfunction "2_2") (pintype "passive"))
      (node (ref "R326") (pin "1") (pinfunction "1_1") (pintype "passive"))
    )
    (net (code "38") (name "Net-(M314-G)") (class "Default")
      (node (ref "M314") (pin "1") (pinfunction "G_1") (pintype "passive"))
      (node (ref "R336") (pin "2") (pinfunction "2_2") (pintype "passive"))
      (node (ref "R341") (pin "1") (pinfunction "1_1") (pintype "passive"))
    )
    (net (code "39") (name "Net-(M314-S)") (class "Default")
      (node (ref "M314") (pin "2") (pinfunction "S_2") (pintype "passive"))
      (node (ref "R337") (pin "1") (pinfunction "1_1") (pintype "passive"))
    )
    (net (code "40") (name "Net-(U300-IN+)") (class "Default")
      (node (ref "R320") (pin "2") (pinfunction "2_2") (pintype "passive"))
      (node (ref "R323") (pin "1") (pinfunction "1_1") (pintype "passive"))
      (node (ref "U300") (pin "C1") (pinfunction "IN+_C1") (pintype "passive"))
    )
    (net (code "41") (name "VCARR") (class "Default")
      (node (ref "C300") (pin "2") (pinfunction "2_2") (pintype "passive"))
      (node (ref "C301") (pin "2") (pinfunction "2_2") (pintype "passive"))
      (node (ref "D300") (pin "2") (pinfunction "A_2") (pintype "passive"))
      (node (ref "D305") (pin "1") (pinfunction "K_1") (pintype "passive"))
      (node (ref "TP302") (pin "1") (pinfunction "1_1") (pintype "passive"))
    )
    (net (code "42") (name "VCHG_RAIL") (class "Default")
      (node (ref "C306") (pin "1") (pinfunction "1_1") (pintype "passive"))
      (node (ref "C307") (pin "2") (pinfunction "2_2") (pintype "passive"))
      (node (ref "C317") (pin "1") (pinfunction "1_1") (pintype "passive"))
      (node (ref "TP321") (pin "1") (pinfunction "1_1") (pintype "passive"))
      (node (ref "U315") (pin "14") (pinfunction "VOUT_14") (pintype "power_in"))
    )
    (net (code "43") (name "VRECT") (class "Default")
      (node (ref "C310") (pin "2") (pinfunction "2_2") (pintype "passive"))
      (node (ref "C311") (pin "2") (pinfunction "2_2") (pintype "passive"))
      (node (ref "C318") (pin "2") (pinfunction "2_2") (pintype "passive"))
      (node (ref "D300") (pin "1") (pinfunction "K_1") (pintype "passive"))
      (node (ref "D301") (pin "1") (pinfunction "K_1") (pintype "passive"))
      (node (ref "D307") (pin "2") (pinfunction "2_2") (pintype "passive"))
      (node (ref "J302") (pin "2") (pinfunction "2_2") (pintype "passive"))
      (node (ref "M300") (pin "3") (pinfunction "D_3") (pintype "passive"))
      (node (ref "M305") (pin "2") (pinfunction "S_2") (pintype "passive"))
      (node (ref "R310") (pin "1") (pinfunction "1_1") (pintype "passive"))
      (node (ref "R315") (pin "1") (pinfunction "1_1") (pintype "passive"))
      (node (ref "R316") (pin "1") (pinfunction "1_1") (pintype "passive"))
      (node (ref "R317") (pin "1") (pinfunction "1_1") (pintype "passive"))
      (node (ref "R324") (pin "1") (pinfunction "1_1") (pintype "passive"))
      (node (ref "R325") (pin "1") (pinfunction "1_1") (pintype "passive"))
      (node (ref "TP308") (pin "1") (pinfunction "1_1") (pintype "passive"))
      (node (ref "U315") (pin "2") (pinfunction "PVIN_2") (pintype "power_in"))
      (node (ref "U315") (pin "3") (pinfunction "VIN_3") (pintype "power_in"))
      (node (ref "U315") (pin "4") (pinfunction "RUN_4") (pintype "input"))
    )
    (net (code "44") (name "unconnected-(J302-Pad1)") (class "Default")
      (node (ref "J302") (pin "1") (pinfunction "1_1") (pintype "passive+no_connect"))
    )
    (net (code "45") (name "unconnected-(J302-Pad3)") (class "Default")
      (node (ref "J302") (pin "3") (pinfunction "3_3") (pintype "passive+no_connect"))
    )
    (net (code "46") (name "unconnected-(U300-NC-PadB2)") (class "Default")
      (node (ref "U300") (pin "B2") (pinfunction "NC_B2") (pintype "power_in+no_connect"))
    )
    (net (code "47") (name "unconnected-(U302-NC-PadB2)") (class "Default")
      (node (ref "U302") (pin "B2") (pinfunction "NC_B2") (pintype "power_in+no_connect"))
    )
    (net (code "48") (name "unconnected-(U313-NC-PadB2)") (class "Default")
      (node (ref "U313") (pin "B2") (pinfunction "NC_B2") (pintype "power_in+no_connect"))
    )
    (net (code "49") (name "unconnected-(U314-NC-PadB2)") (class "Default")
      (node (ref "U314") (pin "B2") (pinfunction "NC_B2") (pintype "power_in+no_connect"))
    )
    (net (code "50") (name "unconnected-(U315-NC-Pad17)") (class "Default")
      (node (ref "U315") (pin "17") (pinfunction "NC_17") (pintype "passive+no_connect"))
    )
  )
)
